# RMS_to_DC_1.net
KiCad netlist of a schematic drawn in Altium Designer
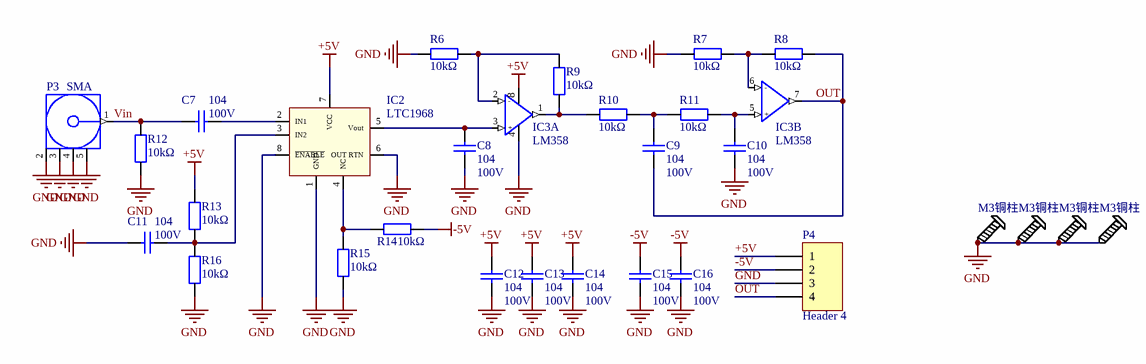
[diagram p0: RMS_to_DC_1.SchDoc]

(export (version "E")
  (design (tool "Eeschema 10.0.6"))
  (components
    (comp (ref "C7")
      (value "叠层陶瓷电容")
      (footprint "C0603")
      (description "无极性电容")
      (fields (field (name "CAPACITY") "104") (field (name "VOLTAGE") "100V"))
      (libsource (lib "原理图库") (part "104"))
    )
    (comp (ref "C8")
      (value "叠层陶瓷电容")
      (footprint "C0603")
      (description "无极性电容")
      (fields (field (name "CAPACITY") "104") (field (name "VOLTAGE") "100V"))
      (libsource (lib "原理图库") (part "104"))
    )
    (comp (ref "C9")
      (value "叠层陶瓷电容")
      (footprint "C0603")
      (description "无极性电容")
      (fields (field (name "CAPACITY") "104") (field (name "VOLTAGE") "100V"))
      (libsource (lib "原理图库") (part "104"))
    )
    (comp (ref "C10")
      (value "叠层陶瓷电容")
      (footprint "C0603")
      (description "无极性电容")
      (fields (field (name "CAPACITY") "104") (field (name "VOLTAGE") "100V"))
      (libsource (lib "原理图库") (part "104"))
    )
    (comp (ref "C11")
      (value "叠层陶瓷电容")
      (footprint "C0603")
      (description "无极性电容")
      (fields (field (name "CAPACITY") "104") (field (name "VOLTAGE") "100V"))
      (libsource (lib "原理图库") (part "104"))
    )
    (comp (ref "C12")
      (value "叠层陶瓷电容")
      (footprint "C0603")
      (description "无极性电容")
      (fields (field (name "CAPACITY") "104") (field (name "VOLTAGE") "100V"))
      (libsource (lib "原理图库") (part "104"))
    )
    (comp (ref "C13")
      (value "叠层陶瓷电容")
      (footprint "C0603")
      (description "无极性电容")
      (fields (field (name "CAPACITY") "104") (field (name "VOLTAGE") "100V"))
      (libsource (lib "原理图库") (part "104"))
    )
    (comp (ref "C14")
      (value "叠层陶瓷电容")
      (footprint "C0603")
      (description "无极性电容")
      (fields (field (name "CAPACITY") "104") (field (name "VOLTAGE") "100V"))
      (libsource (lib "原理图库") (part "104"))
    )
    (comp (ref "C15")
      (value "叠层陶瓷电容")
      (footprint "C0603")
      (description "无极性电容")
      (fields (field (name "CAPACITY") "104") (field (name "VOLTAGE") "100V"))
      (libsource (lib "原理图库") (part "104"))
    )
    (comp (ref "C16")
      (value "叠层陶瓷电容")
      (footprint "C0603")
      (description "无极性电容")
      (fields (field (name "CAPACITY") "104") (field (name "VOLTAGE") "100V"))
      (libsource (lib "原理图库") (part "104"))
    )
    (comp (ref "IC2")
      (value "LTC1968")
      (footprint "MSOP-8")
      (description "RMS")
      (libsource (lib "原理图库") (part "LTC1968"))
    )
    (comp (ref "IC3")
      (value "LM358")
      (footprint "SOP-8(体宽3.8mm)")
      (description "运放")
      (fields (field (name "TYPE") "LM358"))
      (libsource (lib "原理图库") (part "LM358"))
    )
    (comp (ref "P3")
      (value "SMA")
      (footprint "SMA-夹板")
      (description "射频座")
      (libsource (lib "原理图库") (part "SMA"))
    )
    (comp (ref "P4")
      (value "Header 4")
      (footprint "HDR1X4")
      (description "Header, 4-Pin")
      (fields (field (name "PUBLISHER") "Altium Limited"))
      (libsource (lib "Miscellaneous Connectors") (part "Header 4"))
    )
    (comp (ref "R6")
      (value "贴片电阻")
      (footprint "R0603")
      (description "贴片/直插电阻")
      (fields (field (name "RESISTANCE") "10kΩ"))
      (libsource (lib "原理图库") (part "10kΩ"))
    )
    (comp (ref "R7")
      (value "贴片电阻")
      (footprint "R0603")
      (description "贴片/直插电阻")
      (fields (field (name "RESISTANCE") "10kΩ"))
      (libsource (lib "原理图库") (part "10kΩ"))
    )
    (comp (ref "R8")
      (value "贴片电阻")
      (footprint "R0603")
      (description "贴片/直插电阻")
      (fields (field (name "RESISTANCE") "10kΩ"))
      (libsource (lib "原理图库") (part "10kΩ"))
    )
    (comp (ref "R9")
      (value "贴片电阻")
      (footprint "R0603")
      (description "贴片/直插电阻")
      (fields (field (name "RESISTANCE") "10kΩ"))
      (libsource (lib "原理图库") (part "10kΩ"))
    )
    (comp (ref "R10")
      (value "贴片电阻")
      (footprint "R0603")
      (description "贴片/直插电阻")
      (fields (field (name "RESISTANCE") "10kΩ"))
      (libsource (lib "原理图库") (part "10kΩ"))
    )
    (comp (ref "R11")
      (value "贴片电阻")
      (footprint "R0603")
      (description "贴片/直插电阻")
      (fields (field (name "RESISTANCE") "10kΩ"))
      (libsource (lib "原理图库") (part "10kΩ"))
    )
    (comp (ref "R12")
      (value "贴片电阻")
      (footprint "R0603")
      (description "贴片/直插电阻")
      (fields (field (name "RESISTANCE") "10kΩ"))
      (libsource (lib "原理图库") (part "10kΩ"))
    )
    (comp (ref "R13")
      (value "贴片电阻")
      (footprint "R0603")
      (description "贴片/直插电阻")
      (fields (field (name "RESISTANCE") "10kΩ"))
      (libsource (lib "原理图库") (part "10kΩ"))
    )
    (comp (ref "R14")
      (value "贴片电阻")
      (footprint "R0603")
      (description "贴片/直插电阻")
      (fields (field (name "RESISTANCE") "10kΩ"))
      (libsource (lib "原理图库") (part "10kΩ"))
    )
    (comp (ref "R15")
      (value "贴片电阻")
      (footprint "R0603")
      (description "贴片/直插电阻")
      (fields (field (name "RESISTANCE") "10kΩ"))
      (libsource (lib "原理图库") (part "10kΩ"))
    )
    (comp (ref "R16")
      (value "贴片电阻")
      (footprint "R0603")
      (description "贴片/直插电阻")
      (fields (field (name "RESISTANCE") "10kΩ"))
      (libsource (lib "原理图库") (part "10kΩ"))
    )
    (comp (ref "S5") (value "M3铜柱") (footprint "M3") (libsource (lib "原理图库") (part "M3铜柱")))
    (comp (ref "S6") (value "M3铜柱") (footprint "M3") (libsource (lib "原理图库") (part "M3铜柱")))
    (comp (ref "S7") (value "M3铜柱") (footprint "M3") (libsource (lib "原理图库") (part "M3铜柱")))
    (comp (ref "S8") (value "M3铜柱") (footprint "M3") (libsource (lib "原理图库") (part "M3铜柱")))
  )
  (nets
    (net (code "1") (name "+5V") (class "Default")
      (node (ref "C12") (pin "2") (pintype "passive"))
      (node (ref "C13") (pin "2") (pintype "passive"))
      (node (ref "C14") (pin "2") (pintype "passive"))
      (node (ref "IC2") (pin "7") (pinfunction "VCC_7") (pintype "passive"))
      (node (ref "IC3") (pin "8") (pinfunction "vcc_8") (pintype "passive"))
      (node (ref "P4") (pin "1") (pinfunction "1_1") (pintype "passive"))
      (node (ref "R13") (pin "2") (pintype "passive"))
    )
    (net (code "2") (name "-5V") (class "Default")
      (node (ref "C15") (pin "2") (pintype "passive"))
      (node (ref "C16") (pin "2") (pintype "passive"))
      (node (ref "P4") (pin "2") (pinfunction "2_2") (pintype "passive"))
      (node (ref "R14") (pin "1") (pintype "passive"))
    )
    (net (code "3") (name "/OUT") (class "Default")
      (node (ref "C9") (pin "1") (pintype "passive"))
      (node (ref "IC3") (pin "7") (pinfunction "out_7") (pintype "output"))
      (node (ref "P4") (pin "4") (pinfunction "4_4") (pintype "passive"))
      (node (ref "R8") (pin "2") (pintype "passive"))
    )
    (net (code "4") (name "/Vin") (class "Default")
      (node (ref "C7") (pin "1") (pintype "passive"))
      (node (ref "P3") (pin "1") (pinfunction "1_1") (pintype "output"))
      (node (ref "R12") (pin "2") (pintype "passive"))
    )
    (net (code "5") (name "GND") (class "Default")
      (node (ref "C10") (pin "1") (pintype "passive"))
      (node (ref "C11") (pin "1") (pintype "passive"))
      (node (ref "C12") (pin "1") (pintype "passive"))
      (node (ref "C13") (pin "1") (pintype "passive"))
      (node (ref "C14") (pin "1") (pintype "passive"))
      (node (ref "C15") (pin "1") (pintype "passive"))
      (node (ref "C16") (pin "1") (pintype "passive"))
      (node (ref "C8") (pin "1") (pintype "passive"))
      (node (ref "IC2") (pin "1") (pinfunction "GND_1") (pintype "passive"))
      (node (ref "IC2") (pin "6") (pinfunction "OUT_RTN_6") (pintype "passive"))
      (node (ref "IC2") (pin "8") (pinfunction "~{ENABLE}_8") (pintype "passive"))
      (node (ref "IC3") (pin "4") (pinfunction "vee_4") (pintype "passive"))
      (node (ref "P3") (pin "2") (pinfunction "2_2") (pintype "passive"))
      (node (ref "P3") (pin "3") (pinfunction "3_3") (pintype "passive"))
      (node (ref "P3") (pin "4") (pinfunction "4_4") (pintype "passive"))
      (node (ref "P3") (pin "5") (pinfunction "5_5") (pintype "passive"))
      (node (ref "P4") (pin "3") (pinfunction "3_3") (pintype "passive"))
      (node (ref "R12") (pin "1") (pintype "passive"))
      (node (ref "R15") (pin "1") (pintype "passive"))
      (node (ref "R16") (pin "1") (pintype "passive"))
      (node (ref "R6") (pin "1") (pintype "passive"))
      (node (ref "R7") (pin "1") (pintype "passive"))
      (node (ref "S5") (pin "1") (pinfunction "GND_1") (pintype "passive"))
      (node (ref "S6") (pin "1") (pinfunction "GND_1") (pintype "passive"))
      (node (ref "S7") (pin "1") (pinfunction "GND_1") (pintype "passive"))
      (node (ref "S8") (pin "1") (pinfunction "GND_1") (pintype "passive"))
    )
    (net (code "6") (name "Net-(C9-Pad2)") (class "Default")
      (node (ref "C9") (pin "2") (pintype "passive"))
      (node (ref "R10") (pin "1") (pintype "passive"))
      (node (ref "R11") (pin "2") (pintype "passive"))
    )
    (net (code "7") (name "Net-(IC2-IN1)") (class "Default")
      (node (ref "C7") (pin "2") (pintype "passive"))
      (node (ref "IC2") (pin "2") (pinfunction "IN1_2") (pintype "passive"))
    )
    (net (code "8") (name "Net-(IC2-IN2)") (class "Default")
      (node (ref "C11") (pin "2") (pintype "passive"))
      (node (ref "IC2") (pin "3") (pinfunction "IN2_3") (pintype "passive"))
      (node (ref "R13") (pin "1") (pintype "passive"))
      (node (ref "R16") (pin "2") (pintype "passive"))
    )
    (net (code "9") (name "Net-(IC2-NC)") (class "Default")
      (node (ref "IC2") (pin "4") (pinfunction "NC_4") (pintype "passive"))
      (node (ref "R14") (pin "2") (pintype "passive"))
      (node (ref "R15") (pin "2") (pintype "passive"))
    )
    (net (code "10") (name "Net-(IC2-Vout)") (class "Default")
      (node (ref "C8") (pin "2") (pintype "passive"))
      (node (ref "IC2") (pin "5") (pinfunction "Vout_5") (pintype "passive"))
      (node (ref "IC3") (pin "3") (pinfunction "+_3") (pintype "input"))
    )
    (net (code "11") (name "Net-(IC3A--)") (class "Default")
      (node (ref "IC3") (pin "2") (pinfunction "-_2") (pintype "input"))
      (node (ref "R6") (pin "2") (pintype "passive"))
      (node (ref "R9") (pin "1") (pintype "passive"))
    )
    (net (code "12") (name "Net-(IC3A-out)") (class "Default")
      (node (ref "IC3") (pin "1") (pinfunction "out_1") (pintype "output"))
      (node (ref "R10") (pin "2") (pintype "passive"))
      (node (ref "R9") (pin "2") (pintype "passive"))
    )
    (net (code "13") (name "Net-(IC3B-+)") (class "Default")
      (node (ref "C10") (pin "2") (pintype "passive"))
      (node (ref "IC3") (pin "5") (pinfunction "+_5") (pintype "input"))
      (node (ref "R11") (pin "1") (pintype "passive"))
    )
    (net (code "14") (name "Net-(IC3B--)") (class "Default")
      (node (ref "IC3") (pin "6") (pinfunction "-_6") (pintype "input"))
      (node (ref "R7") (pin "2") (pintype "passive"))
      (node (ref "R8") (pin "1") (pintype "passive"))
    )
  )
)
